# uklad-eagle.net
KiCad netlist of a schematic drawn in EAGLE
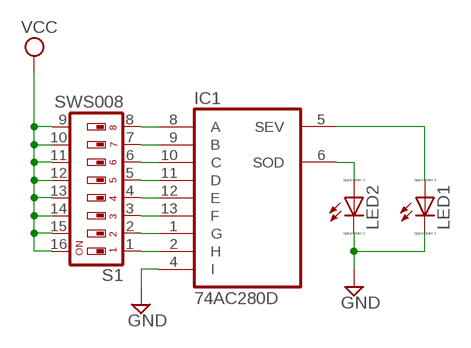
[diagram p0: schematic, sheet 1]

(export (version "E")
  (design (tool "Eeschema 10.0.6"))
  (components
    (comp (ref "IC1")
      (value "74AC280D")
      (footprint "eagle-import:SO14")
      (libsource (lib "eagle-import") (part "74280DAC"))
    )
    (comp (ref "LED1")
      (value "LED_E")
      (footprint "eagle-import:LED_1206")
      (libsource (lib "eagle-import") (part "LED_E"))
    )
    (comp (ref "LED2")
      (value "LED_E")
      (footprint "eagle-import:LED_1206")
      (libsource (lib "eagle-import") (part "LED_E"))
    )
    (comp (ref "S1")
      (value "SWS008")
      (footprint "eagle-import:SMS-008")
      (libsource (lib "eagle-import") (part "SWS008"))
    )
  )
  (nets
    (net (code "1") (name "GND") (class "Default")
      (node (ref "IC1") (pin "4") (pinfunction "I_4") (pintype "input"))
      (node (ref "LED1") (pin "C") (pinfunction "C_C") (pintype "passive"))
      (node (ref "LED2") (pin "C") (pinfunction "C_C") (pintype "passive"))
    )
    (net (code "2") (name "Net-(IC1A-A)") (class "Default")
      (node (ref "IC1") (pin "8") (pinfunction "A_8") (pintype "input"))
      (node (ref "S1") (pin "8") (pinfunction "8_8") (pintype "passive"))
    )
    (net (code "3") (name "Net-(IC1A-B)") (class "Default")
      (node (ref "IC1") (pin "9") (pinfunction "B_9") (pintype "input"))
      (node (ref "S1") (pin "7") (pinfunction "7_7") (pintype "passive"))
    )
    (net (code "4") (name "Net-(IC1A-C)") (class "Default")
      (node (ref "IC1") (pin "10") (pinfunction "C_10") (pintype "input"))
      (node (ref "S1") (pin "6") (pinfunction "6_6") (pintype "passive"))
    )
    (net (code "5") (name "Net-(IC1A-D)") (class "Default")
      (node (ref "IC1") (pin "11") (pinfunction "D_11") (pintype "input"))
      (node (ref "S1") (pin "5") (pinfunction "5_5") (pintype "passive"))
    )
    (net (code "6") (name "Net-(IC1A-E)") (class "Default")
      (node (ref "IC1") (pin "12") (pinfunction "E_12") (pintype "input"))
      (node (ref "S1") (pin "4") (pinfunction "4_4") (pintype "passive"))
    )
    (net (code "7") (name "Net-(IC1A-F)") (class "Default")
      (node (ref "IC1") (pin "13") (pinfunction "F_13") (pintype "input"))
      (node (ref "S1") (pin "3") (pinfunction "3_3") (pintype "passive"))
    )
    (net (code "8") (name "Net-(IC1A-G)") (class "Default")
      (node (ref "IC1") (pin "1") (pinfunction "G_1") (pintype "input"))
      (node (ref "S1") (pin "2") (pinfunction "2_2") (pintype "passive"))
    )
    (net (code "9") (name "Net-(IC1A-H)") (class "Default")
      (node (ref "IC1") (pin "2") (pinfunction "H_2") (pintype "input"))
      (node (ref "S1") (pin "1") (pinfunction "1_1") (pintype "passive"))
    )
    (net (code "10") (name "Net-(IC1A-SEV)") (class "Default")
      (node (ref "IC1") (pin "5") (pinfunction "SEV_5") (pintype "output"))
      (node (ref "LED1") (pin "A") (pinfunction "A_A") (pintype "passive"))
    )
    (net (code "11") (name "Net-(IC1A-SOD)") (class "Default")
      (node (ref "IC1") (pin "6") (pinfunction "SOD_6") (pintype "output"))
      (node (ref "LED2") (pin "A") (pinfunction "A_A") (pintype "passive"))
    )
    (net (code "12") (name "VCC") (class "Default")
      (node (ref "S1") (pin "10") (pinfunction "10_10") (pintype "passive"))
      (node (ref "S1") (pin "11") (pinfunction "11_11") (pintype "passive"))
      (node (ref "S1") (pin "12") (pinfunction "12_12") (pintype "passive"))
      (node (ref "S1") (pin "13") (pinfunction "13_13") (pintype "passive"))
      (node (ref "S1") (pin "14") (pinfunction "14_14") (pintype "passive"))
      (node (ref "S1") (pin "15") (pinfunction "15_15") (pintype "passive"))
      (node (ref "S1") (pin "16") (pinfunction "16_16") (pintype "passive"))
      (node (ref "S1") (pin "9") (pinfunction "9_9") (pintype "passive"))
    )
  )
)
